# STM32_microcontroller_IOs.net
KiCad netlist of a schematic drawn in Altium Designer
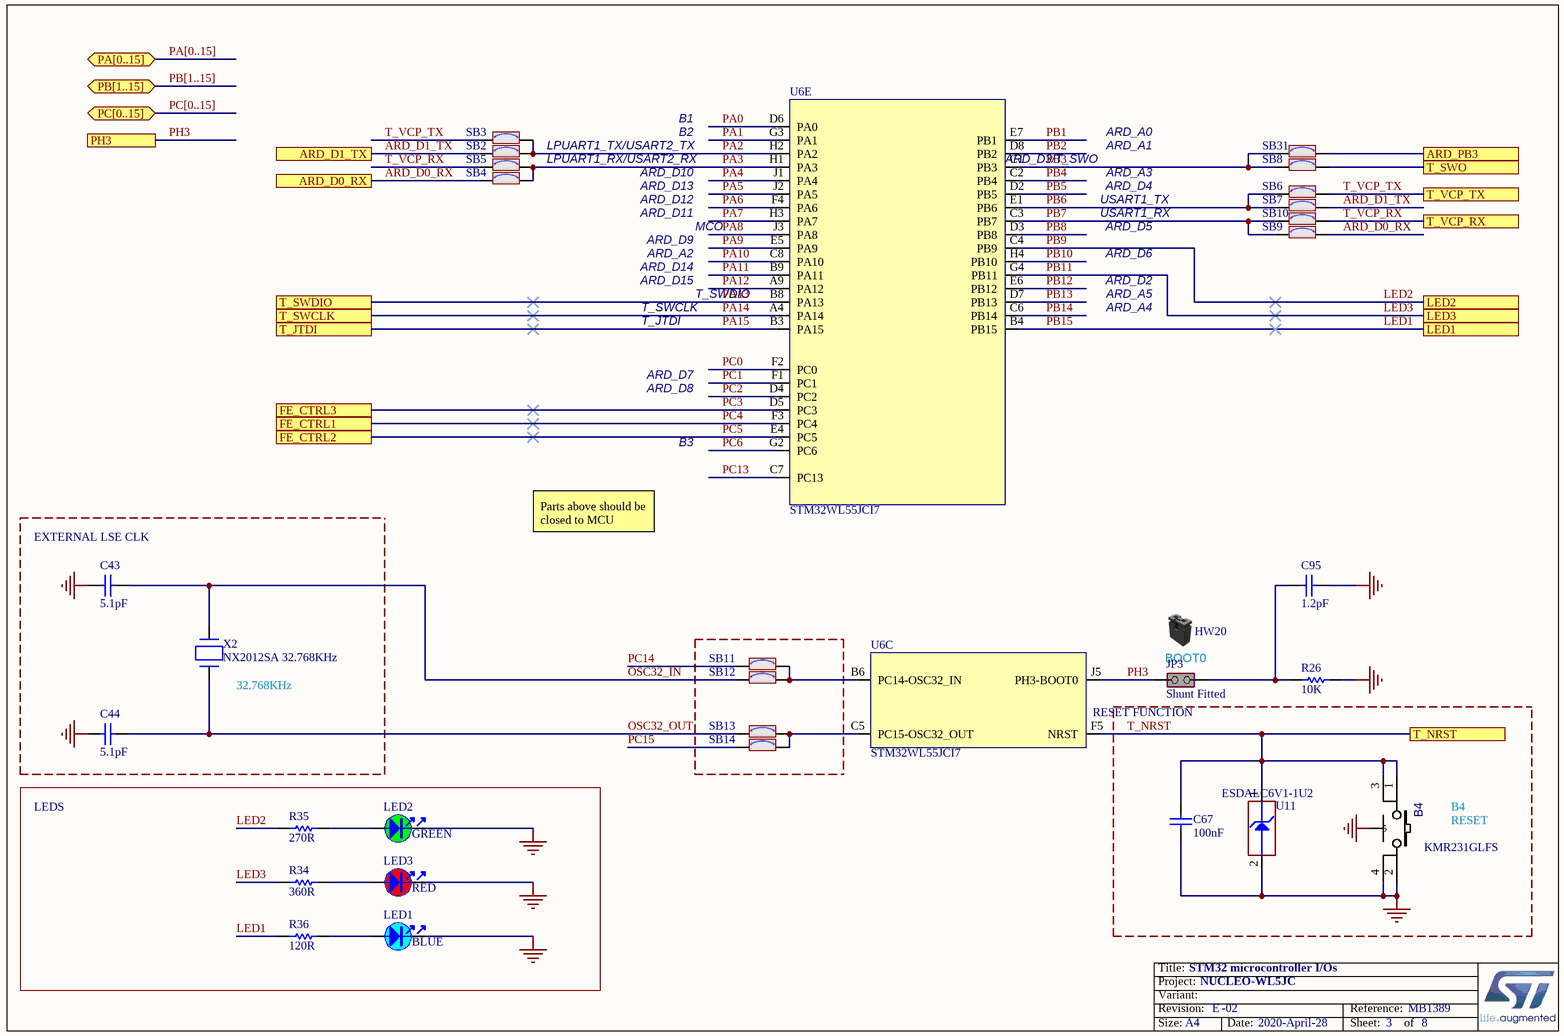
[diagram p0: STM32_microcontroller_IOs.SchDoc]

(export (version "E")
  (design (tool "Eeschema 10.0.6"))
  (components
    (comp (ref "B4")
      (value "KMR231GLFS")
      (footprint "SWI_C&K_Y78B23110FP__ITT_KMR231GLFS")
      (description "Microminiature Tact Switch for SMT - KMR 2 Series - 1.9 mm height")
      (fields
        (field (name "INTERNAL_PART_NUMBER") "MCD-01485")
        (field (name "MANUFACTURER") "C&K")
        (field (name "PROVIDED_BY") "SUBCO")
      )
      (libsource (lib "MCD_PARTS_database") (part "SW-PUSH-CMS_KMR2_BLACK"))
    )
    (comp (ref "C43")
      (value "5.1pF")
      (footprint "C0402")
      (description "Capacitor, MLCC, 5.1pF, 50V, NPO, +-0.25pF, 0402, T=0.5mm")
      (fields
        (field (name "INTERNAL_PART_NUMBER") "MCD-00003")
        (field (name "MANUFACTURER_PART_NUMBER") "CC0402CRNPO9BN5R1")
        (field (name "PROVIDED_BY") "SUBCO")
      )
      (libsource (lib "MCD_PARTS_database") (part "Capacitor"))
    )
    (comp (ref "C44")
      (value "5.1pF")
      (footprint "C0402")
      (description "Capacitor, MLCC, 5.1pF, 50V, NPO, +-0.25pF, 0402, T=0.5mm")
      (fields
        (field (name "INTERNAL_PART_NUMBER") "MCD-00003")
        (field (name "MANUFACTURER_PART_NUMBER") "CC0402CRNPO9BN5R1")
        (field (name "PROVIDED_BY") "SUBCO")
      )
      (libsource (lib "MCD_PARTS_database") (part "Capacitor"))
    )
    (comp (ref "C67")
      (value "100nF")
      (footprint "C0402")
      (description "Capacitor, MLCC, 100nF, 16V, X7R, 10%, 0402, T=0,5mm")
      (fields
        (field (name "INTERNAL_PART_NUMBER") "MCD-00102")
        (field (name "MANUFACTURER_PART_NUMBER") "CC0402KRX7R7BB104")
        (field (name "PROVIDED_BY") "SUBCO")
      )
      (libsource (lib "MCD_PARTS_database") (part "Capacitor"))
    )
    (comp (ref "C95")
      (value "1.2pF")
      (footprint "C0402")
      (description "Capacitor, High Q type for high frequency and high power, SMD, 1.2pF, 50V, 0,05pf, 0402")
      (fields (field (name "INTERNAL_PART_NUMBER") "MCD-02065") (field (name "MANUFACTURER") "MURATA"))
      (libsource (lib "MCD_PARTS_database") (part "Capacitor"))
    )
    (comp (ref "HW20")
      (value "~")
      (description "SHUNT 2.54mm BLACK")
      (fields
        (field (name "INTERNAL_PART_NUMBER") "MCD-00043")
        (field (name "MANUFACTURER_PART_NUMBER") "SNT-100-BK-G")
        (field (name "PROVIDED_BY") "SUBCO")
      )
      (libsource (lib "MCD_PARTS_database") (part "Shunt Black 2.54mm"))
    )
    (comp (ref "JP3")
      (value "Shunt Fitted")
      (footprint "CON_SAMTEC_TSW-102-07-G-S")
      (description "Header, 2x1, 2,54mm, VR, TH, Height 5.84mm/2.54mm - Shunt Fitted by default")
      (fields
        (field (name "INTERNAL_PART_NUMBER") "MCD-00683")
        (field (name "MANUFACTURER_PART_NUMBER") "TSW-102-07-x-S")
        (field (name "PROVIDED_BY") "SUBCO")
      )
      (libsource (lib "MCD_PARTS_database") (part "Jumper_Header 2x1 Fitted"))
    )
    (comp (ref "LED1")
      (value "BLUE")
      (footprint "LED_0603_OSRAM_LB-Q39G-L2OO-35-1_BLUE_1A2K_H0P4")
      (description "LED Blue, 0603 SMD, Forward Voltage Min=2,8V, Max=3,8V")
      (fields
        (field (name "INTERNAL_PART_NUMBER") "MCD-00585")
        (field (name "MANUFACTURER_PART_NUMBER") "LB Q39G-L2OO-35-1")
        (field (name "PROVIDED_BY") "SUBCO")
      )
      (libsource (lib "MCD_PARTS_database") (part "LED_blue"))
    )
    (comp (ref "LED2")
      (value "GREEN")
      (footprint "LED_0603_OSRAM_LG-Q396-PS-35_GREEN_1A2K_H0P4")
      (description "LED Green, 0603 SMD, Forward Voltage Typ=2V, Max=2.5V")
      (fields
        (field (name "INTERNAL_PART_NUMBER") "MCD-00588")
        (field (name "MANUFACTURER_PART_NUMBER") "LG Q396-PS-35")
        (field (name "PROVIDED_BY") "SUBCO")
      )
      (libsource (lib "MCD_PARTS_database") (part "LED_green"))
    )
    (comp (ref "LED3")
      (value "RED")
      (footprint "LED_0603_VISHAY_VLMS1300-GS08_RED_1A2K_H0P8")
      (description "LED Red, 0603 SMD, 2V Forward Voltage")
      (fields
        (field (name "INTERNAL_PART_NUMBER") "MCD-00587")
        (field (name "MANUFACTURER_PART_NUMBER") "VLMS1300-GS08")
        (field (name "PROVIDED_BY") "SUBCO")
      )
      (libsource (lib "MCD_PARTS_database") (part "LED_red"))
    )
    (comp (ref "R26")
      (value "10K")
      (footprint "R0603")
      (description "Resistor,10K,0603,1%,1/10W")
      (fields
        (field (name "INTERNAL_PART_NUMBER") "MCD-00220")
        (field (name "MANUFACTURER_PART_NUMBER") "RC0603FR-0710KL")
        (field (name "PROVIDED_BY") "SUBCO")
      )
      (libsource (lib "MCD_PARTS_database") (part "Resistor"))
    )
    (comp (ref "R34")
      (value "360R")
      (footprint "R0402")
      (description "Resistor,360R,0402,1%,1/16W")
      (fields
        (field (name "INTERNAL_PART_NUMBER") "MCD-00461")
        (field (name "MANUFACTURER_PART_NUMBER") "RC0402FR-07360RL")
        (field (name "PROVIDED_BY") "SUBCO")
      )
      (libsource (lib "MCD_PARTS_database") (part "Resistor"))
    )
    (comp (ref "R35")
      (value "270R")
      (footprint "R0402")
      (description "Resistor,270R,0402,1%,1/16W")
      (fields
        (field (name "INTERNAL_PART_NUMBER") "MCD-00441")
        (field (name "MANUFACTURER_PART_NUMBER") "RC0402FR-07270RL")
        (field (name "PROVIDED_BY") "SUBCO")
      )
      (libsource (lib "MCD_PARTS_database") (part "Resistor"))
    )
    (comp (ref "R36")
      (value "120R")
      (footprint "R0402")
      (description "Resistor,120R,0402,1%,1/16W")
      (fields
        (field (name "INTERNAL_PART_NUMBER") "MCD-00194")
        (field (name "MANUFACTURER_PART_NUMBER") "RC0402FR-07120RL")
        (field (name "PROVIDED_BY") "SUBCO")
      )
      (libsource (lib "MCD_PARTS_database") (part "Resistor"))
    )
    (comp (ref "SB2")
      (value "~")
      (footprint "SOLDER-BRIDGE_R0603-0R")
      (description "Solder Bridge ON")
      (fields
        (field (name "INTERNAL_PART_NUMBER") "MCD-00071")
        (field (name "MANUFACTURER_PART_NUMBER") "RC0603JR-070RL")
        (field (name "PROVIDED_BY") "SUBCO")
      )
      (libsource (lib "") (part "SB_ON_1"))
    )
    (comp (ref "SB3")
      (value "~")
      (footprint "SOLDER-BRIDGE_R0603-0R")
      (description "Solder Bridge ON")
      (fields
        (field (name "INTERNAL_PART_NUMBER") "MCD-00071")
        (field (name "MANUFACTURER_PART_NUMBER") "RC0603JR-070RL")
        (field (name "PROVIDED_BY") "SUBCO")
      )
      (libsource (lib "MCD_PARTS_database") (part "SB_ON"))
    )
    (comp (ref "SB4")
      (value "~")
      (footprint "SOLDER-BRIDGE_R0603-0R")
      (description "Solder Bridge ON")
      (fields
        (field (name "INTERNAL_PART_NUMBER") "MCD-00071")
        (field (name "MANUFACTURER_PART_NUMBER") "RC0603JR-070RL")
        (field (name "PROVIDED_BY") "SUBCO")
      )
      (libsource (lib "") (part "SB_ON_1"))
    )
    (comp (ref "SB5")
      (value "~")
      (footprint "SOLDER-BRIDGE_R0603-0R")
      (description "Solder Bridge ON")
      (fields
        (field (name "INTERNAL_PART_NUMBER") "MCD-00071")
        (field (name "MANUFACTURER_PART_NUMBER") "RC0603JR-070RL")
        (field (name "PROVIDED_BY") "SUBCO")
      )
      (libsource (lib "MCD_PARTS_database") (part "SB_ON"))
    )
    (comp (ref "SB6")
      (value "~")
      (footprint "SOLDER-BRIDGE_R0603-0R")
      (description "Solder Bridge ON")
      (fields
        (field (name "INTERNAL_PART_NUMBER") "MCD-00071")
        (field (name "MANUFACTURER_PART_NUMBER") "RC0603JR-070RL")
        (field (name "PROVIDED_BY") "SUBCO")
      )
      (libsource (lib "MCD_PARTS_database") (part "SB_ON"))
    )
    (comp (ref "SB7")
      (value "~")
      (footprint "SOLDER-BRIDGE_R0603-0R")
      (description "Solder Bridge ON")
      (fields
        (field (name "INTERNAL_PART_NUMBER") "MCD-00071")
        (field (name "MANUFACTURER_PART_NUMBER") "RC0603JR-070RL")
        (field (name "PROVIDED_BY") "SUBCO")
      )
      (libsource (lib "") (part "SB_ON_1"))
    )
    (comp (ref "SB8")
      (value "~")
      (footprint "SOLDER-BRIDGE_R0603-0R")
      (description "Solder Bridge ON")
      (fields
        (field (name "INTERNAL_PART_NUMBER") "MCD-00071")
        (field (name "MANUFACTURER_PART_NUMBER") "RC0603JR-070RL")
        (field (name "PROVIDED_BY") "SUBCO")
      )
      (libsource (lib "MCD_PARTS_database") (part "SB_ON"))
    )
    (comp (ref "SB9")
      (value "~")
      (footprint "SOLDER-BRIDGE_R0603-0R")
      (description "Solder Bridge ON")
      (fields
        (field (name "INTERNAL_PART_NUMBER") "MCD-00071")
        (field (name "MANUFACTURER_PART_NUMBER") "RC0603JR-070RL")
        (field (name "PROVIDED_BY") "SUBCO")
      )
      (libsource (lib "") (part "SB_ON_1"))
    )
    (comp (ref "SB10")
      (value "~")
      (footprint "SOLDER-BRIDGE_R0603-0R")
      (description "Solder Bridge ON")
      (fields
        (field (name "INTERNAL_PART_NUMBER") "MCD-00071")
        (field (name "MANUFACTURER_PART_NUMBER") "RC0603JR-070RL")
        (field (name "PROVIDED_BY") "SUBCO")
      )
      (libsource (lib "MCD_PARTS_database") (part "SB_ON"))
    )
    (comp (ref "SB11")
      (value "~")
      (footprint "SOLDER-BRIDGE_R0603-0R")
      (description "Solder Bridge ON")
      (fields
        (field (name "INTERNAL_PART_NUMBER") "MCD-00071")
        (field (name "MANUFACTURER_PART_NUMBER") "RC0603JR-070RL")
        (field (name "PROVIDED_BY") "SUBCO")
      )
      (libsource (lib "MCD_PARTS_database") (part "SB_ON"))
    )
    (comp (ref "SB12")
      (value "~")
      (footprint "SOLDER-BRIDGE_R0603-0R")
      (description "Solder Bridge ON")
      (fields
        (field (name "INTERNAL_PART_NUMBER") "MCD-00071")
        (field (name "MANUFACTURER_PART_NUMBER") "RC0603JR-070RL")
        (field (name "PROVIDED_BY") "SUBCO")
      )
      (libsource (lib "MCD_PARTS_database") (part "SB_ON"))
    )
    (comp (ref "SB13")
      (value "~")
      (footprint "SOLDER-BRIDGE_R0603-0R")
      (description "Solder Bridge ON")
      (fields
        (field (name "INTERNAL_PART_NUMBER") "MCD-00071")
        (field (name "MANUFACTURER_PART_NUMBER") "RC0603JR-070RL")
        (field (name "PROVIDED_BY") "SUBCO")
      )
      (libsource (lib "MCD_PARTS_database") (part "SB_ON"))
    )
    (comp (ref "SB14")
      (value "~")
      (footprint "SOLDER-BRIDGE_R0603-0R")
      (description "Solder Bridge ON")
      (fields
        (field (name "INTERNAL_PART_NUMBER") "MCD-00071")
        (field (name "MANUFACTURER_PART_NUMBER") "RC0603JR-070RL")
        (field (name "PROVIDED_BY") "SUBCO")
      )
      (libsource (lib "MCD_PARTS_database") (part "SB_ON"))
    )
    (comp (ref "SB31")
      (value "~")
      (footprint "SOLDER-BRIDGE_R0603-0R")
      (description "Solder Bridge ON")
      (fields
        (field (name "INTERNAL_PART_NUMBER") "MCD-00071")
        (field (name "MANUFACTURER_PART_NUMBER") "RC0603JR-070RL")
        (field (name "PROVIDED_BY") "SUBCO")
      )
      (libsource (lib "MCD_PARTS_database") (part "SB_ON"))
    )
    (comp (ref "U6")
      (value "STM32WL55JCI7")
      (footprint "ICC_UFBGA73_5X5_P050")
      (description "Multiprotocol Wireless 32-bit MCUwith LPWAN Sub-GHz radio solution")
      (fields
        (field (name "INTERNAL_PART_NUMBER") "MCD-01435")
        (field (name "MANUFACTURER") "STMICROELECTRONICS")
      )
      (libsource (lib "MCD_PARTS_database") (part "STM32WL5x_BGA73"))
    )
    (comp (ref "U11")
      (value "ESDALC6V1-1U2")
      (footprint "ESD_ST0201")
      (description "ESD protection 6V1")
      (fields
        (field (name "INTERNAL_PART_NUMBER") "MCD-00170")
        (field (name "MANUFACTURER") "STMICROELECTRONICS")
        (field (name "PROVIDED_BY") "SUBCO with ST control")
      )
      (libsource (lib "MCD_PARTS_database") (part "ESD-TRANSIL"))
    )
    (comp (ref "X2")
      (value "NX2012SA 32.768KHz")
      (footprint "CRY_NX2012SA_2P")
      (description "Crystal 32.768kHz, 6pF, -+20ppm, 80Kohm max, SMD")
      (fields
        (field (name "INTERNAL_PART_NUMBER") "MCD-01479")
        (field (name "MANUFACTURER_PART_NUMBER") "NX2012SA 32.768KHz EXS00A-MU00527")
        (field (name "PROVIDED_BY") "SUBCO")
      )
      (libsource (lib "MCD_PARTS_database") (part "XTAL_2_PINS"))
    )
  )
  (nets
    (net (code "7") (name "/ARD_D0_RX") (class "Default")
      (node (ref "SB4") (pin "2") (pinfunction "2_2") (pintype "passive"))
      (node (ref "SB9") (pin "1") (pinfunction "1_1") (pintype "passive"))
    )
    (net (code "8") (name "/ARD_D1_TX") (class "Default")
      (node (ref "SB2") (pin "2") (pinfunction "2_2") (pintype "passive"))
      (node (ref "SB7") (pin "1") (pinfunction "1_1") (pintype "passive"))
    )
    (net (code "9") (name "/ARD_PB3") (class "Default")
      (node (ref "SB31") (pin "2") (pinfunction "2_2") (pintype "passive"))
    )
    (net (code "10") (name "/OSC32_IN") (class "Default")
      (node (ref "C43") (pin "1") (pinfunction "1_1") (pintype "passive"))
      (node (ref "SB12") (pin "1") (pinfunction "1_1") (pintype "passive"))
      (node (ref "X2") (pin "2") (pinfunction "X2_2") (pintype "passive"))
    )
    (net (code "11") (name "/OSC32_OUT") (class "Default")
      (node (ref "C44") (pin "1") (pinfunction "1_1") (pintype "passive"))
      (node (ref "SB13") (pin "1") (pinfunction "1_1") (pintype "passive"))
      (node (ref "X2") (pin "1") (pinfunction "X1_1") (pintype "passive"))
    )
    (net (code "12") (name "/PA0") (class "Default")
      (node (ref "U6") (pin "D6") (pinfunction "PA0_D6") (pintype "passive"))
    )
    (net (code "13") (name "/PA1") (class "Default")
      (node (ref "U6") (pin "G3") (pinfunction "PA1_G3") (pintype "passive"))
    )
    (net (code "14") (name "/PA2") (class "Default")
      (node (ref "SB2") (pin "1") (pinfunction "1_1") (pintype "passive"))
      (node (ref "SB3") (pin "2") (pinfunction "2_2") (pintype "passive"))
      (node (ref "U6") (pin "H2") (pinfunction "PA2_H2") (pintype "passive"))
    )
    (net (code "15") (name "/PA3") (class "Default")
      (node (ref "SB4") (pin "1") (pinfunction "1_1") (pintype "passive"))
      (node (ref "SB5") (pin "2") (pinfunction "2_2") (pintype "passive"))
      (node (ref "U6") (pin "H1") (pinfunction "PA3_H1") (pintype "passive"))
    )
    (net (code "16") (name "/PA4") (class "Default")
      (node (ref "U6") (pin "J1") (pinfunction "PA4_J1") (pintype "passive"))
    )
    (net (code "17") (name "/PA5") (class "Default")
      (node (ref "U6") (pin "J2") (pinfunction "PA5_J2") (pintype "passive"))
    )
    (net (code "18") (name "/PA6") (class "Default")
      (node (ref "U6") (pin "F4") (pinfunction "PA6_F4") (pintype "passive"))
    )
    (net (code "19") (name "/PA7") (class "Default")
      (node (ref "U6") (pin "H3") (pinfunction "PA7_H3") (pintype "passive"))
    )
    (net (code "20") (name "/PA8") (class "Default")
      (node (ref "U6") (pin "J3") (pinfunction "PA8_J3") (pintype "passive"))
    )
    (net (code "21") (name "/PA9") (class "Default")
      (node (ref "U6") (pin "E5") (pinfunction "PA9_E5") (pintype "passive"))
    )
    (net (code "22") (name "/PA10") (class "Default")
      (node (ref "U6") (pin "C8") (pinfunction "PA10_C8") (pintype "passive"))
    )
    (net (code "23") (name "/PA11") (class "Default")
      (node (ref "U6") (pin "B9") (pinfunction "PA11_B9") (pintype "passive"))
    )
    (net (code "24") (name "/PA12") (class "Default")
      (node (ref "U6") (pin "A9") (pinfunction "PA12_A9") (pintype "passive"))
    )
    (net (code "25") (name "/PA13") (class "Default")
      (node (ref "U6") (pin "B8") (pinfunction "PA13_B8") (pintype "passive"))
    )
    (net (code "26") (name "/PA14") (class "Default")
      (node (ref "U6") (pin "A4") (pinfunction "PA14_A4") (pintype "passive"))
    )
    (net (code "27") (name "/PA15") (class "Default")
      (node (ref "U6") (pin "B3") (pinfunction "PA15_B3") (pintype "passive"))
    )
    (net (code "29") (name "/PB1") (class "Default")
      (node (ref "U6") (pin "E7") (pinfunction "PB1_E7") (pintype "passive"))
    )
    (net (code "30") (name "/PB2") (class "Default")
      (node (ref "U6") (pin "D8") (pinfunction "PB2_D8") (pintype "passive"))
    )
    (net (code "31") (name "/PB3") (class "Default")
      (node (ref "SB31") (pin "1") (pinfunction "1_1") (pintype "passive"))
      (node (ref "SB8") (pin "1") (pinfunction "1_1") (pintype "passive"))
      (node (ref "U6") (pin "C1") (pinfunction "PB3_C1") (pintype "passive"))
    )
    (net (code "32") (name "/PB4") (class "Default")
      (node (ref "U6") (pin "C2") (pinfunction "PB4_C2") (pintype "passive"))
    )
    (net (code "33") (name "/PB5") (class "Default")
      (node (ref "U6") (pin "D2") (pinfunction "PB5_D2") (pintype "passive"))
    )
    (net (code "34") (name "/PB6") (class "Default")
      (node (ref "SB6") (pin "1") (pinfunction "1_1") (pintype "passive"))
      (node (ref "SB7") (pin "2") (pinfunction "2_2") (pintype "passive"))
      (node (ref "U6") (pin "E1") (pinfunction "PB6_E1") (pintype "passive"))
    )
    (net (code "35") (name "/PB7") (class "Default")
      (node (ref "SB10") (pin "1") (pinfunction "1_1") (pintype "passive"))
      (node (ref "SB9") (pin "2") (pinfunction "2_2") (pintype "passive"))
      (node (ref "U6") (pin "C3") (pinfunction "PB7_C3") (pintype "passive"))
    )
    (net (code "36") (name "/PB8") (class "Default")
      (node (ref "U6") (pin "D3") (pinfunction "PB8_D3") (pintype "passive"))
    )
    (net (code "37") (name "/PB9") (class "Default")
      (node (ref "R35") (pin "1") (pinfunction "1_1") (pintype "passive"))
      (node (ref "U6") (pin "C4") (pinfunction "PB9_C4") (pintype "passive"))
    )
    (net (code "38") (name "/PB10") (class "Default")
      (node (ref "U6") (pin "H4") (pinfunction "PB10_H4") (pintype "passive"))
    )
    (net (code "39") (name "/PB11") (class "Default")
      (node (ref "R34") (pin "1") (pinfunction "1_1") (pintype "passive"))
      (node (ref "U6") (pin "G4") (pinfunction "PB11_G4") (pintype "passive"))
    )
    (net (code "40") (name "/PB12") (class "Default")
      (node (ref "U6") (pin "E6") (pinfunction "PB12_E6") (pintype "passive"))
    )
    (net (code "41") (name "/PB13") (class "Default")
      (node (ref "U6") (pin "D7") (pinfunction "PB13_D7") (pintype "passive"))
    )
    (net (code "42") (name "/PB14") (class "Default")
      (node (ref "U6") (pin "C6") (pinfunction "PB14_C6") (pintype "passive"))
    )
    (net (code "43") (name "/PB15") (class "Default")
      (node (ref "R36") (pin "1") (pinfunction "1_1") (pintype "passive"))
      (node (ref "U6") (pin "B4") (pinfunction "PB15_B4") (pintype "passive"))
    )
    (net (code "45") (name "/PC0") (class "Default")
      (node (ref "U6") (pin "F2") (pinfunction "PC0_F2") (pintype "passive"))
    )
    (net (code "46") (name "/PC1") (class "Default")
      (node (ref "U6") (pin "F1") (pinfunction "PC1_F1") (pintype "passive"))
    )
    (net (code "47") (name "/PC2") (class "Default")
      (node (ref "U6") (pin "D4") (pinfunction "PC2_D4") (pintype "passive"))
    )
    (net (code "48") (name "/PC3") (class "Default")
      (node (ref "U6") (pin "D5") (pinfunction "PC3_D5") (pintype "passive"))
    )
    (net (code "49") (name "/PC4") (class "Default")
      (node (ref "U6") (pin "F3") (pinfunction "PC4_F3") (pintype "passive"))
    )
    (net (code "50") (name "/PC5") (class "Default")
      (node (ref "U6") (pin "E4") (pinfunction "PC5_E4") (pintype "passive"))
    )
    (net (code "51") (name "/PC6") (class "Default")
      (node (ref "U6") (pin "G2") (pinfunction "PC6_G2") (pintype "passive"))
    )
    (net (code "52") (name "/PC13") (class "Default")
      (node (ref "U6") (pin "C7") (pinfunction "PC13_C7") (pintype "passive"))
    )
    (net (code "53") (name "/PC14") (class "Default")
      (node (ref "SB11") (pin "1") (pinfunction "1_1") (pintype "passive"))
    )
    (net (code "54") (name "/PC15") (class "Default")
      (node (ref "SB14") (pin "1") (pinfunction "1_1") (pintype "passive"))
    )
    (net (code "56") (name "/PH3") (class "Default")
      (node (ref "JP3") (pin "1") (pinfunction "COMMON_1") (pintype "passive"))
      (node (ref "U6") (pin "J5") (pinfunction "PH3-BOOT0_J5") (pintype "passive"))
    )
    (net (code "57") (name "/T_NRST") (class "Default")
      (node (ref "B4") (pin "1") (pinfunction "1_1") (pintype "passive"))
      (node (ref "B4") (pin "3") (pinfunction "3_3") (pintype "passive"))
      (node (ref "C67") (pin "2") (pinfunction "2_2") (pintype "passive"))
      (node (ref "U11") (pin "1") (pinfunction "IO1_1") (pintype "passive"))
      (node (ref "U6") (pin "F5") (pinfunction "NRST_F5") (pintype "passive"))
    )
    (net (code "58") (name "/T_SWO") (class "Default")
      (node (ref "SB8") (pin "2") (pinfunction "2_2") (pintype "passive"))
    )
    (net (code "59") (name "/T_VCP_RX") (class "Default")
      (node (ref "SB10") (pin "2") (pinfunction "2_2") (pintype "passive"))
      (node (ref "SB5") (pin "1") (pinfunction "1_1") (pintype "passive"))
    )
    (net (code "60") (name "/T_VCP_TX") (class "Default")
      (node (ref "SB3") (pin "1") (pinfunction "1_1") (pintype "passive"))
      (node (ref "SB6") (pin "2") (pinfunction "2_2") (pintype "passive"))
    )
    (net (code "61") (name "GND") (class "Default")
      (node (ref "B4") (pin "2") (pinfunction "2_2") (pintype "passive"))
      (node (ref "B4") (pin "4") (pinfunction "4_4") (pintype "passive"))
      (node (ref "B4") (pin "5") (pinfunction "5_5") (pintype "passive"))
      (node (ref "C43") (pin "2") (pinfunction "2_2") (pintype "passive"))
      (node (ref "C44") (pin "2") (pinfunction "2_2") (pintype "passive"))
      (node (ref "C67") (pin "1") (pinfunction "1_1") (pintype "passive"))
      (node (ref "C95") (pin "1") (pinfunction "1_1") (pintype "passive"))
      (node (ref "LED1") (pin "2") (pintype "passive"))
      (node (ref "LED2") (pin "2") (pintype "passive"))
      (node (ref "LED3") (pin "2") (pintype "passive"))
      (node (ref "R26") (pin "1") (pinfunction "1_1") (pintype "passive"))
      (node (ref "U11") (pin "2") (pinfunction "GND_2") (pintype "passive"))
    )
    (net (code "62") (name "Net-(JP3-NO)") (class "Default")
      (node (ref "C95") (pin "2") (pinfunction "2_2") (pintype "passive"))
      (node (ref "JP3") (pin "2") (pinfunction "NO_2") (pintype "passive"))
      (node (ref "R26") (pin "2") (pinfunction "2_2") (pintype "passive"))
    )
    (net (code "63") (name "Net-(LED1-Pad1)") (class "Default")
      (node (ref "LED1") (pin "1") (pintype "passive"))
      (node (ref "R36") (pin "2") (pinfunction "2_2") (pintype "passive"))
    )
    (net (code "64") (name "Net-(LED2-Pad1)") (class "Default")
      (node (ref "LED2") (pin "1") (pintype "passive"))
      (node (ref "R35") (pin "2") (pinfunction "2_2") (pintype "passive"))
    )
    (net (code "65") (name "Net-(LED3-Pad1)") (class "Default")
      (node (ref "LED3") (pin "1") (pintype "passive"))
      (node (ref "R34") (pin "2") (pinfunction "2_2") (pintype "passive"))
    )
    (net (code "66") (name "Net-(U6C-PC14-OSC32_IN)") (class "Default")
      (node (ref "SB11") (pin "2") (pinfunction "2_2") (pintype "passive"))
      (node (ref "SB12") (pin "2") (pinfunction "2_2") (pintype "passive"))
      (node (ref "U6") (pin "B6") (pinfunction "PC14-OSC32_IN_B6") (pintype "passive"))
    )
    (net (code "67") (name "Net-(U6C-PC15-OSC32_OUT)") (class "Default")
      (node (ref "SB13") (pin "2") (pinfunction "2_2") (pintype "passive"))
      (node (ref "SB14") (pin "2") (pinfunction "2_2") (pintype "passive"))
      (node (ref "U6") (pin "C5") (pinfunction "PC15-OSC32_OUT_C5") (pintype "passive"))
    )
  )
)
